# R3D2.net
KiCad netlist of a schematic drawn in EAGLE
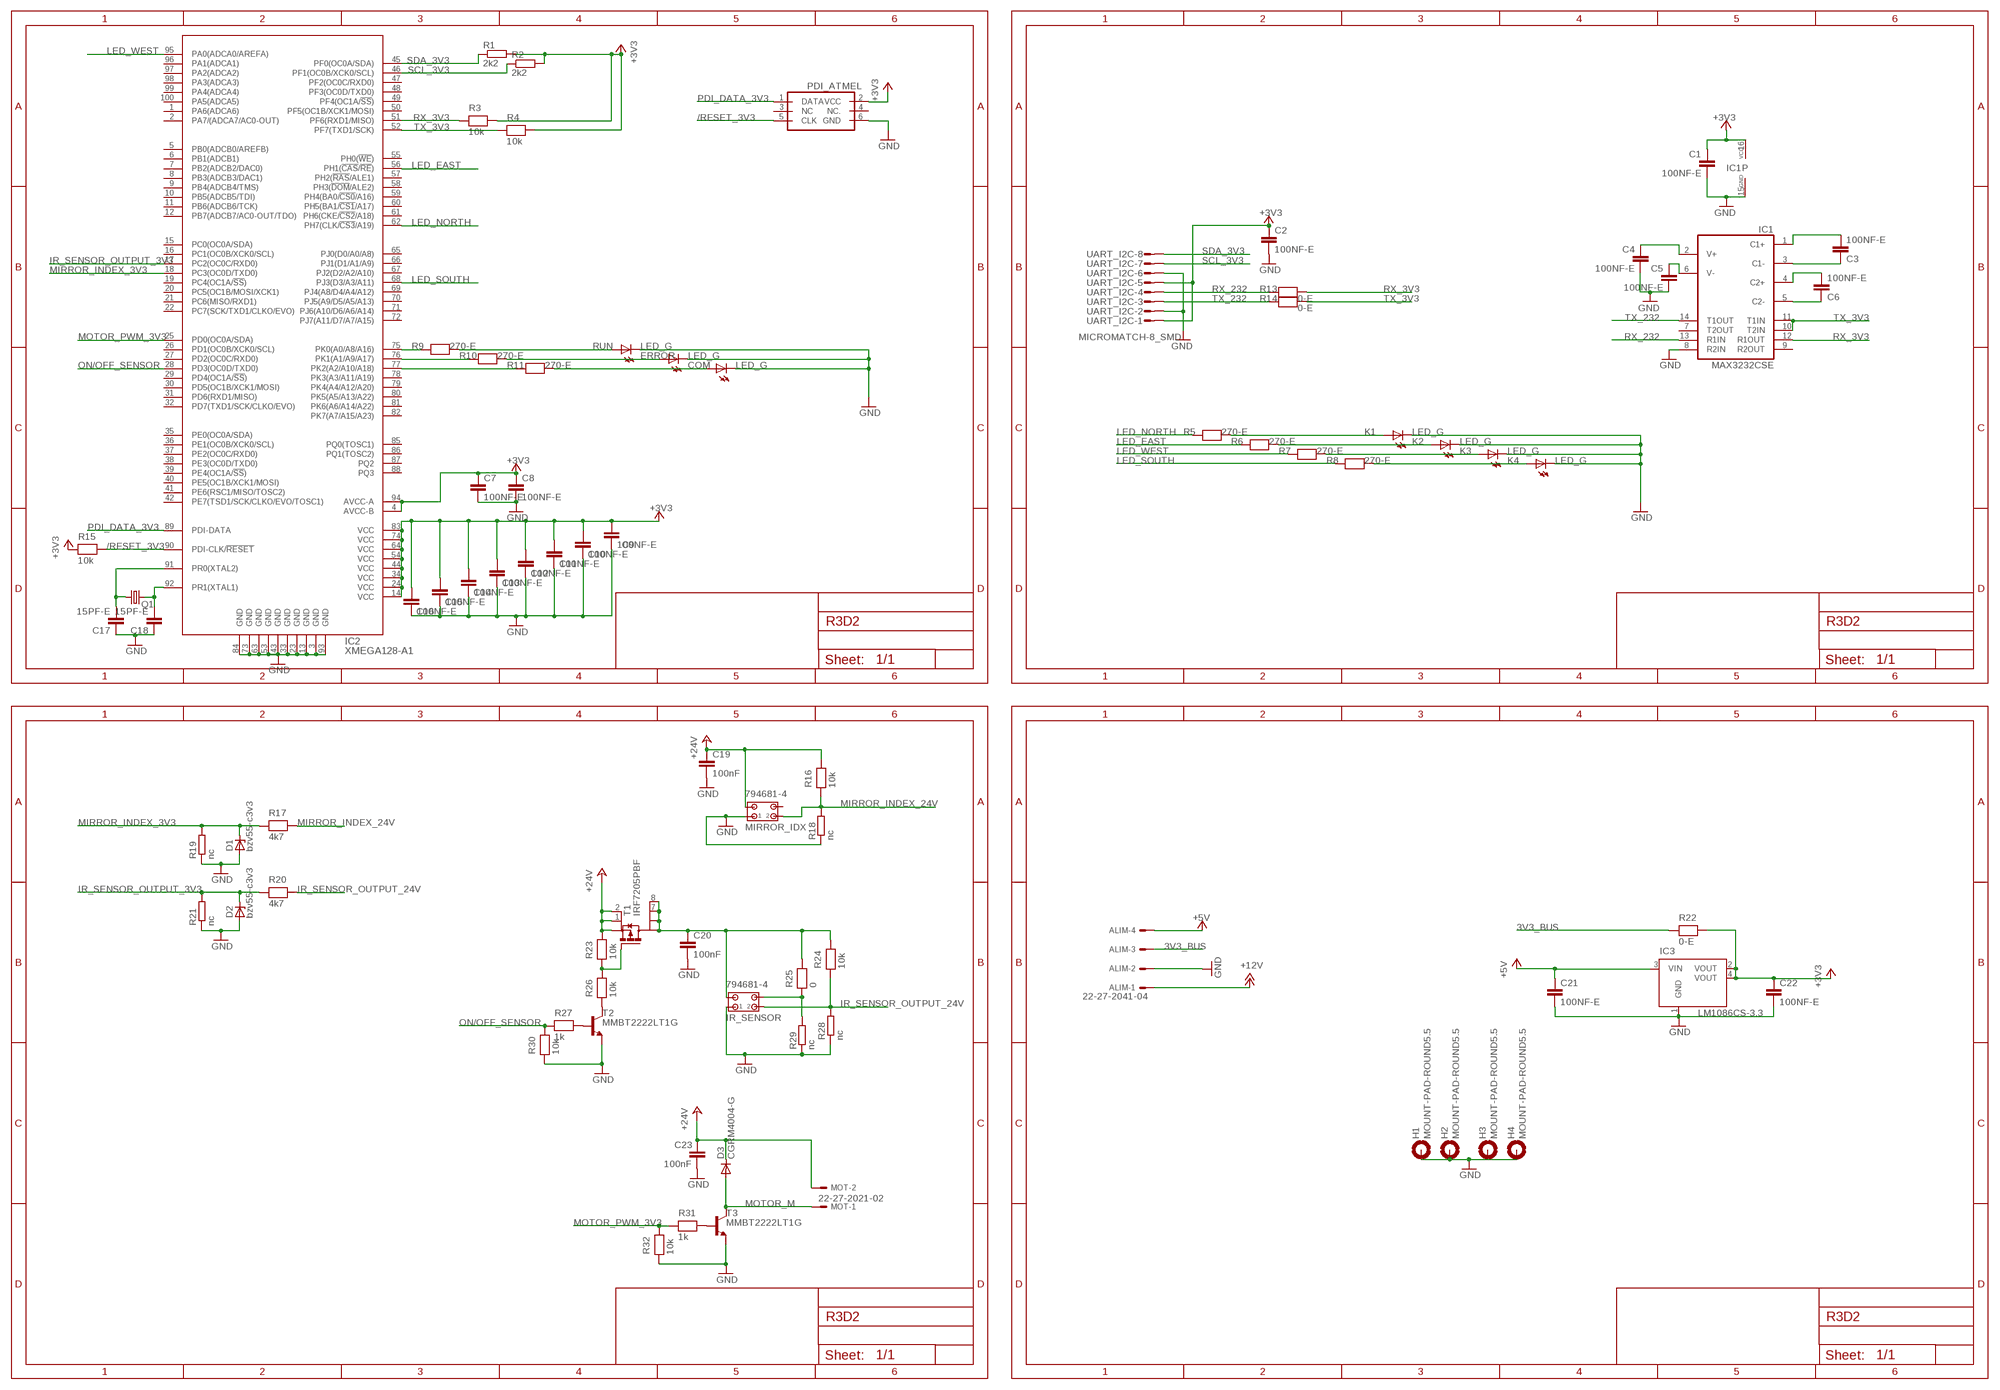
[diagram p0: schematic, sheet 1]

(export (version "E")
  (design (tool "Eeschema 10.0.6"))
  (components
    (comp (ref "ALIM")
      (value "22-27-2041-04")
      (footprint "eagle-import:6410-04")
      (libsource (lib "eagle-import") (part "22-?-0427-2041"))
    )
    (comp (ref "C1")
      (value "100NF-E")
      (footprint "eagle-import:C0805")
      (libsource (lib "eagle-import") (part "100NF-E"))
    )
    (comp (ref "C2")
      (value "100NF-E")
      (footprint "eagle-import:C0805")
      (libsource (lib "eagle-import") (part "100NF-E"))
    )
    (comp (ref "C3")
      (value "100NF-E")
      (footprint "eagle-import:C0805")
      (libsource (lib "eagle-import") (part "100NF-E"))
    )
    (comp (ref "C4")
      (value "100NF-E")
      (footprint "eagle-import:C0805")
      (libsource (lib "eagle-import") (part "100NF-E"))
    )
    (comp (ref "C5")
      (value "100NF-E")
      (footprint "eagle-import:C0805")
      (libsource (lib "eagle-import") (part "100NF-E"))
    )
    (comp (ref "C6")
      (value "100NF-E")
      (footprint "eagle-import:C0805")
      (libsource (lib "eagle-import") (part "100NF-E"))
    )
    (comp (ref "C7")
      (value "100NF-E")
      (footprint "eagle-import:C0805")
      (libsource (lib "eagle-import") (part "100NF-E"))
    )
    (comp (ref "C8")
      (value "100NF-E")
      (footprint "eagle-import:C0805")
      (libsource (lib "eagle-import") (part "100NF-E"))
    )
    (comp (ref "C9")
      (value "100NF-E")
      (footprint "eagle-import:C0805")
      (libsource (lib "eagle-import") (part "100NF-E"))
    )
    (comp (ref "C10")
      (value "100NF-E")
      (footprint "eagle-import:C0805")
      (libsource (lib "eagle-import") (part "100NF-E"))
    )
    (comp (ref "C11")
      (value "100NF-E")
      (footprint "eagle-import:C0805")
      (libsource (lib "eagle-import") (part "100NF-E"))
    )
    (comp (ref "C12")
      (value "100NF-E")
      (footprint "eagle-import:C0805")
      (libsource (lib "eagle-import") (part "100NF-E"))
    )
    (comp (ref "C13")
      (value "100NF-E")
      (footprint "eagle-import:C0805")
      (libsource (lib "eagle-import") (part "100NF-E"))
    )
    (comp (ref "C14")
      (value "100NF-E")
      (footprint "eagle-import:C0805")
      (libsource (lib "eagle-import") (part "100NF-E"))
    )
    (comp (ref "C15")
      (value "100NF-E")
      (footprint "eagle-import:C0805")
      (libsource (lib "eagle-import") (part "100NF-E"))
    )
    (comp (ref "C16")
      (value "100NF-E")
      (footprint "eagle-import:C0805")
      (libsource (lib "eagle-import") (part "100NF-E"))
    )
    (comp (ref "C17")
      (value "15PF-E")
      (footprint "eagle-import:C0805")
      (libsource (lib "eagle-import") (part "15PF-E"))
    )
    (comp (ref "C18")
      (value "15PF-E")
      (footprint "eagle-import:C0805")
      (libsource (lib "eagle-import") (part "15PF-E"))
    )
    (comp (ref "C19")
      (value "100nF")
      (footprint "eagle-import:C0805")
      (libsource (lib "eagle-import") (part "100NF-E"))
    )
    (comp (ref "C20")
      (value "100nF")
      (footprint "eagle-import:C0603")
      (libsource (lib "eagle-import") (part "100NF-F"))
    )
    (comp (ref "C21")
      (value "100NF-E")
      (footprint "eagle-import:C0805")
      (libsource (lib "eagle-import") (part "100NF-E"))
    )
    (comp (ref "C22")
      (value "100NF-E")
      (footprint "eagle-import:C0805")
      (libsource (lib "eagle-import") (part "100NF-E"))
    )
    (comp (ref "C23")
      (value "100nF")
      (footprint "eagle-import:C0805")
      (libsource (lib "eagle-import") (part "100NF-E"))
    )
    (comp (ref "COM")
      (value "LED_G")
      (footprint "eagle-import:CHIP-LED0805")
      (libsource (lib "eagle-import") (part "LED_G"))
    )
    (comp (ref "D1")
      (value "bzv55-c3v3")
      (footprint "eagle-import:SOD80C")
      (libsource (lib "eagle-import") (part "BZV55-C3V3SOD80C"))
    )
    (comp (ref "D2")
      (value "bzv55-c3v3")
      (footprint "eagle-import:SOD80C")
      (libsource (lib "eagle-import") (part "BZV55-C3V3SOD80C"))
    )
    (comp (ref "D3")
      (value "CGRM4004-G")
      (footprint "eagle-import:SOD-123_MINI-SMA")
      (libsource (lib "eagle-import") (part "CGRM400-G4"))
    )
    (comp (ref "ERROR")
      (value "LED_G")
      (footprint "eagle-import:CHIP-LED0805")
      (libsource (lib "eagle-import") (part "LED_G"))
    )
    (comp (ref "H1")
      (value "MOUNT-PAD-ROUND5.5")
      (footprint "eagle-import:5,5-PAD")
      (libsource (lib "eagle-import") (part "MOUNT-PAD-ROUND5.5"))
    )
    (comp (ref "H2")
      (value "MOUNT-PAD-ROUND5.5")
      (footprint "eagle-import:5,5-PAD")
      (libsource (lib "eagle-import") (part "MOUNT-PAD-ROUND5.5"))
    )
    (comp (ref "H3")
      (value "MOUNT-PAD-ROUND5.5")
      (footprint "eagle-import:5,5-PAD")
      (libsource (lib "eagle-import") (part "MOUNT-PAD-ROUND5.5"))
    )
    (comp (ref "H4")
      (value "MOUNT-PAD-ROUND5.5")
      (footprint "eagle-import:5,5-PAD")
      (libsource (lib "eagle-import") (part "MOUNT-PAD-ROUND5.5"))
    )
    (comp (ref "IC1")
      (value "MAX3232CSE")
      (footprint "eagle-import:SO16")
      (libsource (lib "eagle-import") (part "MAX3232SEC"))
    )
    (comp (ref "IC2")
      (value "XMEGA128-A1")
      (footprint "eagle-import:TQFP100")
      (libsource (lib "eagle-import") (part "XMEGA-A1TQFP"))
    )
    (comp (ref "IC3")
      (value "LM1086CS-3.3")
      (footprint "eagle-import:TO263")
      (libsource (lib "eagle-import") (part "LM1086CS-3.3"))
    )
    (comp (ref "IR_SENSOR")
      (value "794681-4")
      (footprint "eagle-import:794681-4")
      (libsource (lib "eagle-import") (part "794681-4"))
    )
    (comp (ref "K1")
      (value "LED_G")
      (footprint "eagle-import:CHIP-LED0805")
      (libsource (lib "eagle-import") (part "LED_G"))
    )
    (comp (ref "K2")
      (value "LED_G")
      (footprint "eagle-import:CHIP-LED0805")
      (libsource (lib "eagle-import") (part "LED_G"))
    )
    (comp (ref "K3")
      (value "LED_G")
      (footprint "eagle-import:CHIP-LED0805")
      (libsource (lib "eagle-import") (part "LED_G"))
    )
    (comp (ref "K4")
      (value "LED_G")
      (footprint "eagle-import:CHIP-LED0805")
      (libsource (lib "eagle-import") (part "LED_G"))
    )
    (comp (ref "MIRROR_IDX")
      (value "794681-4")
      (footprint "eagle-import:794681-4")
      (libsource (lib "eagle-import") (part "794681-4"))
    )
    (comp (ref "MOT")
      (value "22-27-2021-02")
      (footprint "eagle-import:6410-02")
      (libsource (lib "eagle-import") (part "22-?-0227-2021"))
    )
    (comp (ref "PDI_ATMEL")
      (value "PDI_ATMEL")
      (footprint "eagle-import:ML6")
      (libsource (lib "eagle-import") (part "PDI_ATMEL"))
    )
    (comp (ref "Q1")
      (value "CRYSTAL_16MHZ_HC49UP")
      (footprint "eagle-import:HC49UP")
      (libsource (lib "eagle-import") (part "CRYSTAL_16MHZ_HC49UP"))
    )
    (comp (ref "R1")
      (value "2k2")
      (footprint "eagle-import:R0603")
      (libsource (lib "eagle-import") (part "R-EU_R0603"))
    )
    (comp (ref "R2")
      (value "2k2")
      (footprint "eagle-import:R0603")
      (libsource (lib "eagle-import") (part "R-EU_R0603"))
    )
    (comp (ref "R3")
      (value "10k")
      (footprint "eagle-import:R0603")
      (libsource (lib "eagle-import") (part "10K-F"))
    )
    (comp (ref "R4")
      (value "10k")
      (footprint "eagle-import:R0603")
      (libsource (lib "eagle-import") (part "10K-F"))
    )
    (comp (ref "R5")
      (value "270-E")
      (footprint "eagle-import:R0805")
      (libsource (lib "eagle-import") (part "270-E"))
    )
    (comp (ref "R6")
      (value "270-E")
      (footprint "eagle-import:R0805")
      (libsource (lib "eagle-import") (part "270-E"))
    )
    (comp (ref "R7")
      (value "270-E")
      (footprint "eagle-import:R0805")
      (libsource (lib "eagle-import") (part "270-E"))
    )
    (comp (ref "R8")
      (value "270-E")
      (footprint "eagle-import:R0805")
      (libsource (lib "eagle-import") (part "270-E"))
    )
    (comp (ref "R9")
      (value "270-E")
      (footprint "eagle-import:R0805")
      (libsource (lib "eagle-import") (part "270-E"))
    )
    (comp (ref "R10")
      (value "270-E")
      (footprint "eagle-import:R0805")
      (libsource (lib "eagle-import") (part "270-E"))
    )
    (comp (ref "R11")
      (value "270-E")
      (footprint "eagle-import:R0805")
      (libsource (lib "eagle-import") (part "270-E"))
    )
    (comp (ref "R13")
      (value "0-E")
      (footprint "eagle-import:R0805")
      (libsource (lib "eagle-import") (part "0-E"))
    )
    (comp (ref "R14")
      (value "0-E")
      (footprint "eagle-import:R0805")
      (libsource (lib "eagle-import") (part "0-E"))
    )
    (comp (ref "R15")
      (value "10k")
      (footprint "eagle-import:R0603")
      (libsource (lib "eagle-import") (part "10K-F"))
    )
    (comp (ref "R16")
      (value "10k")
      (footprint "eagle-import:R0603")
      (libsource (lib "eagle-import") (part "10K-F"))
    )
    (comp (ref "R17")
      (value "4k7")
      (footprint "eagle-import:R0805")
      (libsource (lib "eagle-import") (part "4K7-E"))
    )
    (comp (ref "R18")
      (value "nc")
      (footprint "eagle-import:R0805")
      (libsource (lib "eagle-import") (part "R-EU_R0805"))
    )
    (comp (ref "R19")
      (value "nc")
      (footprint "eagle-import:R0603")
      (libsource (lib "eagle-import") (part "R-EU_R0603"))
    )
    (comp (ref "R20")
      (value "4k7")
      (footprint "eagle-import:R0805")
      (libsource (lib "eagle-import") (part "4K7-E"))
    )
    (comp (ref "R21")
      (value "nc")
      (footprint "eagle-import:R0603")
      (libsource (lib "eagle-import") (part "R-EU_R0603"))
    )
    (comp (ref "R22")
      (value "0-E")
      (footprint "eagle-import:R0805")
      (libsource (lib "eagle-import") (part "0-E"))
    )
    (comp (ref "R23")
      (value "10k")
      (footprint "eagle-import:R0603")
      (libsource (lib "eagle-import") (part "10K-F"))
    )
    (comp (ref "R24")
      (value "10k")
      (footprint "eagle-import:R0603")
      (libsource (lib "eagle-import") (part "10K-F"))
    )
    (comp (ref "R25")
      (value "0")
      (footprint "eagle-import:R0603")
      (libsource (lib "eagle-import") (part "0-F"))
    )
    (comp (ref "R26")
      (value "10k")
      (footprint "eagle-import:R0603")
      (libsource (lib "eagle-import") (part "10K-F"))
    )
    (comp (ref "R27")
      (value "1k")
      (footprint "eagle-import:R0603")
      (libsource (lib "eagle-import") (part "1K-F"))
    )
    (comp (ref "R28")
      (value "nc")
      (footprint "eagle-import:R0603")
      (libsource (lib "eagle-import") (part "R-EU_R0603"))
    )
    (comp (ref "R29")
      (value "nc")
      (footprint "eagle-import:R0603")
      (libsource (lib "eagle-import") (part "R-EU_R0603"))
    )
    (comp (ref "R30")
      (value "10k")
      (footprint "eagle-import:R0603")
      (libsource (lib "eagle-import") (part "10K-F"))
    )
    (comp (ref "R31")
      (value "1k")
      (footprint "eagle-import:R0603")
      (libsource (lib "eagle-import") (part "1K-F"))
    )
    (comp (ref "R32")
      (value "10k")
      (footprint "eagle-import:R0603")
      (libsource (lib "eagle-import") (part "10K-F"))
    )
    (comp (ref "RUN")
      (value "LED_G")
      (footprint "eagle-import:CHIP-LED0805")
      (libsource (lib "eagle-import") (part "LED_G"))
    )
    (comp (ref "T1")
      (value "IRF7205PBF")
      (footprint "eagle-import:SO8")
      (libsource (lib "eagle-import") (part "IRF7205PBF"))
    )
    (comp (ref "T2")
      (value "MMBT2222LT1G")
      (footprint "eagle-import:SOT23-BEC")
      (libsource (lib "eagle-import") (part "-NPN-SOT23-BECMMBT2222ALT1"))
    )
    (comp (ref "T3")
      (value "MMBT2222LT1G")
      (footprint "eagle-import:SOT23-BEC")
      (libsource (lib "eagle-import") (part "-NPN-SOT23-BECMMBT2222ALT1"))
    )
    (comp (ref "UART_I2C")
      (value "MICROMATCH-8_SMD")
      (footprint "eagle-import:MICROMATCH-8_SMD")
      (libsource (lib "eagle-import") (part "MICROMATCH-8_SMD"))
    )
  )
  (nets
    (net (code "1") (name "+3V3") (class "Default")
      (node (ref "C1") (pin "1") (pinfunction "1_1") (pintype "passive"))
      (node (ref "C10") (pin "1") (pinfunction "1_1") (pintype "passive"))
      (node (ref "C11") (pin "1") (pinfunction "1_1") (pintype "passive"))
      (node (ref "C12") (pin "1") (pinfunction "1_1") (pintype "passive"))
      (node (ref "C13") (pin "1") (pinfunction "1_1") (pintype "passive"))
      (node (ref "C14") (pin "1") (pinfunction "1_1") (pintype "passive"))
      (node (ref "C15") (pin "1") (pinfunction "1_1") (pintype "passive"))
      (node (ref "C16") (pin "1") (pinfunction "1_1") (pintype "passive"))
      (node (ref "C2") (pin "1") (pinfunction "1_1") (pintype "passive"))
      (node (ref "C22") (pin "1") (pinfunction "1_1") (pintype "passive"))
      (node (ref "C7") (pin "1") (pinfunction "1_1") (pintype "passive"))
      (node (ref "C8") (pin "1") (pinfunction "1_1") (pintype "passive"))
      (node (ref "C9") (pin "1") (pinfunction "1_1") (pintype "passive"))
      (node (ref "IC1") (pin "16") (pinfunction "VCC_16") (pintype "power_in"))
      (node (ref "IC2") (pin "14") (pinfunction "VCC_14") (pintype "power_in"))
      (node (ref "IC2") (pin "24") (pinfunction "VCC_24") (pintype "power_in"))
      (node (ref "IC2") (pin "34") (pinfunction "VCC_34") (pintype "power_in"))
      (node (ref "IC2") (pin "4") (pinfunction "AVCC-B_4") (pintype "power_in"))
      (node (ref "IC2") (pin "44") (pinfunction "VCC_44") (pintype "power_in"))
      (node (ref "IC2") (pin "54") (pinfunction "VCC_54") (pintype "power_in"))
      (node (ref "IC2") (pin "64") (pinfunction "VCC_64") (pintype "power_in"))
      (node (ref "IC2") (pin "74") (pinfunction "VCC_74") (pintype "power_in"))
      (node (ref "IC2") (pin "83") (pinfunction "VCC_83") (pintype "power_in"))
      (node (ref "IC2") (pin "94") (pinfunction "AVCC-A_94") (pintype "power_in"))
      (node (ref "IC3") (pin "2") (pinfunction "VOUT_2") (pintype "bidirectional"))
      (node (ref "IC3") (pin "4") (pinfunction "VOUT_4") (pintype "bidirectional"))
      (node (ref "PDI_ATMEL") (pin "2") (pinfunction "VCC_2") (pintype "passive"))
      (node (ref "R1") (pin "2") (pinfunction "2_2") (pintype "passive"))
      (node (ref "R15") (pin "1") (pinfunction "1_1") (pintype "bidirectional"))
      (node (ref "R2") (pin "2") (pinfunction "2_2") (pintype "passive"))
      (node (ref "R22") (pin "2") (pinfunction "2_2") (pintype "bidirectional"))
      (node (ref "R3") (pin "2") (pinfunction "2_2") (pintype "bidirectional"))
      (node (ref "R4") (pin "2") (pinfunction "2_2") (pintype "bidirectional"))
      (node (ref "UART_I2C") (pin "1") (pinfunction "S_1") (pintype "passive"))
      (node (ref "UART_I2C") (pin "5") (pinfunction "S_5") (pintype "passive"))
    )
    (net (code "2") (name "+5V") (class "Default")
      (node (ref "ALIM") (pin "4") (pinfunction "S_4") (pintype "passive"))
      (node (ref "C21") (pin "1") (pinfunction "1_1") (pintype "passive"))
      (node (ref "IC3") (pin "3") (pinfunction "VIN_3") (pintype "bidirectional"))
    )
    (net (code "3") (name "+12V") (class "Default")
      (node (ref "ALIM") (pin "1") (pinfunction "S_1") (pintype "passive"))
    )
    (net (code "4") (name "+24V") (class "Default")
      (node (ref "C19") (pin "1") (pinfunction "1_1") (pintype "passive"))
      (node (ref "C23") (pin "1") (pinfunction "1_1") (pintype "passive"))
      (node (ref "D3") (pin "C") (pinfunction "C_C") (pintype "passive"))
      (node (ref "MIRROR_IDX") (pin "3") (pinfunction "3_3") (pintype "passive"))
      (node (ref "MOT") (pin "2") (pinfunction "S_2") (pintype "passive"))
      (node (ref "R16") (pin "2") (pinfunction "2_2") (pintype "bidirectional"))
      (node (ref "R23") (pin "2") (pinfunction "2_2") (pintype "bidirectional"))
      (node (ref "T1") (pin "1") (pinfunction "S_1") (pintype "power_in"))
      (node (ref "T1") (pin "2") (pinfunction "S_2") (pintype "power_in"))
      (node (ref "T1") (pin "3") (pinfunction "S_3") (pintype "power_in"))
    )
    (net (code "5") (name "/3V3_BUS") (class "Default")
      (node (ref "ALIM") (pin "3") (pinfunction "S_3") (pintype "passive"))
      (node (ref "R22") (pin "1") (pinfunction "1_1") (pintype "bidirectional"))
    )
    (net (code "6") (name "/IR_SENSOR_OUTPUT_3V3") (class "Default")
      (node (ref "D2") (pin "C") (pinfunction "C_C") (pintype "passive"))
      (node (ref "IC2") (pin "17") (pinfunction "PC2(OC0C/RXD0)_17") (pintype "bidirectional"))
      (node (ref "R20") (pin "1") (pinfunction "1_1") (pintype "bidirectional"))
      (node (ref "R21") (pin "2") (pinfunction "2_2") (pintype "passive"))
    )
    (net (code "7") (name "/IR_SENSOR_OUTPUT_24V") (class "Default")
      (node (ref "IR_SENSOR") (pin "2") (pinfunction "2_2") (pintype "passive"))
      (node (ref "R20") (pin "2") (pinfunction "2_2") (pintype "bidirectional"))
      (node (ref "R24") (pin "1") (pinfunction "1_1") (pintype "bidirectional"))
      (node (ref "R28") (pin "2") (pinfunction "2_2") (pintype "passive"))
    )
    (net (code "8") (name "/LED_EAST") (class "Default")
      (node (ref "IC2") (pin "56") (pinfunction "PH1(~{CAS}/~{RE})_56") (pintype "bidirectional"))
      (node (ref "R6") (pin "1") (pinfunction "1_1") (pintype "bidirectional"))
    )
    (net (code "9") (name "/LED_NORTH") (class "Default")
      (node (ref "IC2") (pin "62") (pinfunction "PH7(CLK/~{CS3}/A19)_62") (pintype "bidirectional"))
      (node (ref "R5") (pin "1") (pinfunction "1_1") (pintype "bidirectional"))
    )
    (net (code "10") (name "/LED_SOUTH") (class "Default")
      (node (ref "IC2") (pin "68") (pinfunction "PJ3(D3/A3/A11)_68") (pintype "bidirectional"))
      (node (ref "R8") (pin "1") (pinfunction "1_1") (pintype "bidirectional"))
    )
    (net (code "11") (name "/LED_WEST") (class "Default")
      (node (ref "IC2") (pin "95") (pinfunction "PA0(ADCA0/AREFA)_95") (pintype "bidirectional"))
      (node (ref "R7") (pin "1") (pinfunction "1_1") (pintype "bidirectional"))
    )
    (net (code "12") (name "/MIRROR_INDEX_3V3") (class "Default")
      (node (ref "D1") (pin "C") (pinfunction "C_C") (pintype "passive"))
      (node (ref "IC2") (pin "18") (pinfunction "PC3(OC0D/TXD0)_18") (pintype "bidirectional"))
      (node (ref "R17") (pin "1") (pinfunction "1_1") (pintype "bidirectional"))
      (node (ref "R19") (pin "2") (pinfunction "2_2") (pintype "passive"))
    )
    (net (code "13") (name "/MIRROR_INDEX_24V") (class "Default")
      (node (ref "MIRROR_IDX") (pin "2") (pinfunction "2_2") (pintype "passive"))
      (node (ref "R16") (pin "1") (pinfunction "1_1") (pintype "bidirectional"))
      (node (ref "R17") (pin "2") (pinfunction "2_2") (pintype "bidirectional"))
      (node (ref "R18") (pin "2") (pinfunction "2_2") (pintype "passive"))
    )
    (net (code "14") (name "/MOTOR_M") (class "Default")
      (node (ref "D3") (pin "A") (pinfunction "A_A") (pintype "passive"))
      (node (ref "MOT") (pin "1") (pinfunction "S_1") (pintype "passive"))
      (node (ref "T3") (pin "C") (pinfunction "C_C") (pintype "passive"))
    )
    (net (code "15") (name "/MOTOR_PWM_3V3") (class "Default")
      (node (ref "IC2") (pin "25") (pinfunction "PD0(OC0A/SDA)_25") (pintype "bidirectional"))
      (node (ref "R31") (pin "1") (pinfunction "1_1") (pintype "bidirectional"))
      (node (ref "R32") (pin "2") (pinfunction "2_2") (pintype "bidirectional"))
    )
    (net (code "16") (name "/ON{slash}OFF_SENSOR") (class "Default")
      (node (ref "IC2") (pin "28") (pinfunction "PD3(OC0D/TXD0)_28") (pintype "bidirectional"))
      (node (ref "R27") (pin "1") (pinfunction "1_1") (pintype "bidirectional"))
      (node (ref "R30") (pin "2") (pinfunction "2_2") (pintype "bidirectional"))
    )
    (net (code "17") (name "/PDI_DATA_3V3") (class "Default")
      (node (ref "IC2") (pin "89") (pinfunction "PDI-DATA_89") (pintype "bidirectional"))
      (node (ref "PDI_ATMEL") (pin "1") (pinfunction "DATA_1") (pintype "passive"))
    )
    (net (code "18") (name "/RX_3V3") (class "Default")
      (node (ref "IC1") (pin "12") (pinfunction "R1OUT_12") (pintype "output"))
      (node (ref "IC2") (pin "51") (pinfunction "PF6(RXD1/MISO)_51") (pintype "bidirectional"))
      (node (ref "R13") (pin "2") (pinfunction "2_2") (pintype "bidirectional"))
      (node (ref "R3") (pin "1") (pinfunction "1_1") (pintype "bidirectional"))
    )
    (net (code "19") (name "/RX_232") (class "Default")
      (node (ref "IC1") (pin "13") (pinfunction "R1IN_13") (pintype "input"))
      (node (ref "R13") (pin "1") (pinfunction "1_1") (pintype "bidirectional"))
      (node (ref "UART_I2C") (pin "4") (pinfunction "S_4") (pintype "passive"))
    )
    (net (code "20") (name "/SCL_3V3") (class "Default")
      (node (ref "IC2") (pin "46") (pinfunction "PF1(OC0B/XCK0/SCL)_46") (pintype "bidirectional"))
      (node (ref "R2") (pin "1") (pinfunction "1_1") (pintype "passive"))
      (node (ref "UART_I2C") (pin "7") (pinfunction "S_7") (pintype "passive"))
    )
    (net (code "21") (name "/SDA_3V3") (class "Default")
      (node (ref "IC2") (pin "45") (pinfunction "PF0(OC0A/SDA)_45") (pintype "bidirectional"))
      (node (ref "R1") (pin "1") (pinfunction "1_1") (pintype "passive"))
      (node (ref "UART_I2C") (pin "8") (pinfunction "S_8") (pintype "passive"))
    )
    (net (code "22") (name "/TX_3V3") (class "Default")
      (node (ref "IC1") (pin "10") (pinfunction "T2IN_10") (pintype "input"))
      (node (ref "IC1") (pin "11") (pinfunction "T1IN_11") (pintype "input"))
      (node (ref "IC2") (pin "52") (pinfunction "PF7(TXD1/SCK)_52") (pintype "bidirectional"))
      (node (ref "R14") (pin "2") (pinfunction "2_2") (pintype "bidirectional"))
      (node (ref "R4") (pin "1") (pinfunction "1_1") (pintype "bidirectional"))
    )
    (net (code "23") (name "/TX_232") (class "Default")
      (node (ref "IC1") (pin "14") (pinfunction "T1OUT_14") (pintype "output"))
      (node (ref "R14") (pin "1") (pinfunction "1_1") (pintype "bidirectional"))
      (node (ref "UART_I2C") (pin "3") (pinfunction "S_3") (pintype "passive"))
    )
    (net (code "24") (name "/{slash}RESET_3V3") (class "Default")
      (node (ref "IC2") (pin "90") (pinfunction "PDI-CLK/~{RESET}_90") (pintype "input"))
      (node (ref "PDI_ATMEL") (pin "5") (pinfunction "CLK_5") (pintype "passive"))
      (node (ref "R15") (pin "2") (pinfunction "2_2") (pintype "bidirectional"))
    )
    (net (code "25") (name "GND") (class "Default")
      (node (ref "ALIM") (pin "2") (pinfunction "S_2") (pintype "passive"))
      (node (ref "C1") (pin "2") (pinfunction "2_2") (pintype "passive"))
      (node (ref "C10") (pin "2") (pinfunction "2_2") (pintype "passive"))
      (node (ref "C11") (pin "2") (pinfunction "2_2") (pintype "passive"))
      (node (ref "C12") (pin "2") (pinfunction "2_2") (pintype "passive"))
      (node (ref "C13") (pin "2") (pinfunction "2_2") (pintype "passive"))
      (node (ref "C14") (pin "2") (pinfunction "2_2") (pintype "passive"))
      (node (ref "C15") (pin "2") (pinfunction "2_2") (pintype "passive"))
      (node (ref "C16") (pin "2") (pinfunction "2_2") (pintype "passive"))
      (node (ref "C17") (pin "1") (pinfunction "1_1") (pintype "passive"))
      (node (ref "C18") (pin "1") (pinfunction "1_1") (pintype "passive"))
      (node (ref "C19") (pin "2") (pinfunction "2_2") (pintype "passive"))
      (node (ref "C2") (pin "2") (pinfunction "2_2") (pintype "passive"))
      (node (ref "C20") (pin "2") (pinfunction "2_2") (pintype "passive"))
      (node (ref "C21") (pin "2") (pinfunction "2_2") (pintype "passive"))
      (node (ref "C22") (pin "2") (pinfunction "2_2") (pintype "passive"))
      (node (ref "C23") (pin "2") (pinfunction "2_2") (pintype "passive"))
      (node (ref "C4") (pin "2") (pinfunction "2_2") (pintype "passive"))
      (node (ref "C5") (pin "2") (pinfunction "2_2") (pintype "passive"))
      (node (ref "C7") (pin "2") (pinfunction "2_2") (pintype "passive"))
      (node (ref "C8") (pin "2") (pinfunction "2_2") (pintype "passive"))
      (node (ref "C9") (pin "2") (pinfunction "2_2") (pintype "passive"))
      (node (ref "COM") (pin "C") (pinfunction "C_C") (pintype "passive"))
      (node (ref "D1") (pin "A") (pinfunction "A_A") (pintype "passive"))
      (node (ref "D2") (pin "A") (pinfunction "A_A") (pintype "passive"))
      (node (ref "ERROR") (pin "C") (pinfunction "C_C") (pintype "passive"))
      (node (ref "H1") (pin "B5,5") (pinfunction "MOUNT_B5,5") (pintype "passive"))
      (node (ref "H2") (pin "B5,5") (pinfunction "MOUNT_B5,5") (pintype "passive"))
      (node (ref "H3") (pin "B5,5") (pinfunction "MOUNT_B5,5") (pintype "passive"))
      (node (ref "H4") (pin "B5,5") (pinfunction "MOUNT_B5,5") (pintype "passive"))
      (node (ref "IC1") (pin "15") (pinfunction "GND_15") (pintype "power_in"))
      (node (ref "IC1") (pin "8") (pinfunction "R2IN_8") (pintype "input"))
      (node (ref "IC2") (pin "13") (pinfunction "GND_13") (pintype "power_in"))
      (node (ref "IC2") (pin "23") (pinfunction "GND_23") (pintype "power_in"))
      (node (ref "IC2") (pin "3") (pinfunction "GND_3") (pintype "power_in"))
      (node (ref "IC2") (pin "33") (pinfunction "GND_33") (pintype "power_in"))
      (node (ref "IC2") (pin "43") (pinfunction "GND_43") (pintype "power_in"))
      (node (ref "IC2") (pin "53") (pinfunction "GND_53") (pintype "power_in"))
      (node (ref "IC2") (pin "63") (pinfunction "GND_63") (pintype "power_in"))
      (node (ref "IC2") (pin "73") (pinfunction "GND_73") (pintype "power_in"))
      (node (ref "IC2") (pin "84") (pinfunction "GND_84") (pintype "power_in"))
      (node (ref "IC2") (pin "93") (pinfunction "GND_93") (pintype "power_in"))
      (node (ref "IC3") (pin "1") (pinfunction "GND_1") (pintype "bidirectional"))
      (node (ref "IR_SENSOR") (pin "1") (pinfunction "1_1") (pintype "passive"))
      (node (ref "K1") (pin "C") (pinfunction "C_C") (pintype "passive"))
      (node (ref "K2") (pin "C") (pinfunction "C_C") (pintype "passive"))
      (node (ref "K3") (pin "C") (pinfunction "C_C") (pintype "passive"))
      (node (ref "K4") (pin "C") (pinfunction "C_C") (pintype "passive"))
      (node (ref "MIRROR_IDX") (pin "1") (pinfunction "1_1") (pintype "passive"))
      (node (ref "PDI_ATMEL") (pin "6") (pinfunction "GND_6") (pintype "passive"))
      (node (ref "R18") (pin "1") (pinfunction "1_1") (pintype "passive"))
      (node (ref "R19") (pin "1") (pinfunction "1_1") (pintype "passive"))
      (node (ref "R21") (pin "1") (pinfunction "1_1") (pintype "passive"))
      (node (ref "R28") (pin "1") (pinfunction "1_1") (pintype "passive"))
      (node (ref "R29") (pin "1") (pinfunction "1_1") (pintype "passive"))
      (node (ref "R30") (pin "1") (pinfunction "1_1") (pintype "bidirectional"))
      (node (ref "R32") (pin "1") (pinfunction "1_1") (pintype "bidirectional"))
      (node (ref "RUN") (pin "C") (pinfunction "C_C") (pintype "passive"))
      (node (ref "T2") (pin "E") (pinfunction "E_E") (pintype "passive"))
      (node (ref "T3") (pin "E") (pinfunction "E_E") (pintype "passive"))
      (node (ref "UART_I2C") (pin "2") (pinfunction "S_2") (pintype "passive"))
      (node (ref "UART_I2C") (pin "6") (pinfunction "S_6") (pintype "passive"))
    )
    (net (code "26") (name "Net-(C20-Pad1)") (class "Default")
      (node (ref "C20") (pin "1") (pinfunction "1_1") (pintype "passive"))
      (node (ref "IR_SENSOR") (pin "3") (pinfunction "3_3") (pintype "passive"))
      (node (ref "R24") (pin "2") (pinfunction "2_2") (pintype "bidirectional"))
      (node (ref "R25") (pin "2") (pinfunction "2_2") (pintype "bidirectional"))
      (node (ref "T1") (pin "5") (pinfunction "D_5") (pintype "power_in"))
      (node (ref "T1") (pin "6") (pinfunction "D_6") (pintype "power_in"))
      (node (ref "T1") (pin "7") (pinfunction "D_7") (pintype "power_in"))
      (node (ref "T1") (pin "8") (pinfunction "D_8") (pintype "power_in"))
    )
    (net (code "27") (name "Net-(COM-PadA)") (class "Default")
      (node (ref "COM") (pin "A") (pinfunction "A_A") (pintype "passive"))
      (node (ref "R11") (pin "2") (pinfunction "2_2") (pintype "bidirectional"))
    )
    (net (code "28") (name "Net-(ERROR-PadA)") (class "Default")
      (node (ref "ERROR") (pin "A") (pinfunction "A_A") (pintype "passive"))
      (node (ref "R10") (pin "2") (pinfunction "2_2") (pintype "bidirectional"))
    )
    (net (code "29") (name "Net-(IC1A-C1+)") (class "Default")
      (node (ref "C3") (pin "1") (pinfunction "1_1") (pintype "passive"))
      (node (ref "IC1") (pin "1") (pinfunction "C1+_1") (pintype "bidirectional"))
    )
    (net (code "30") (name "Net-(IC1A-C1-)") (class "Default")
      (node (ref "C3") (pin "2") (pinfunction "2_2") (pintype "passive"))
      (node (ref "IC1") (pin "3") (pinfunction "C1-_3") (pintype "bidirectional"))
    )
    (net (code "31") (name "Net-(IC1A-C2+)") (class "Default")
      (node (ref "C6") (pin "1") (pinfunction "1_1") (pintype "passive"))
      (node (ref "IC1") (pin "4") (pinfunction "C2+_4") (pintype "bidirectional"))
    )
    (net (code "32") (name "Net-(IC1A-C2-)") (class "Default")
      (node (ref "C6") (pin "2") (pinfunction "2_2") (pintype "passive"))
      (node (ref "IC1") (pin "5") (pinfunction "C2-_5") (pintype "bidirectional"))
    )
    (net (code "33") (name "Net-(IC1A-V+)") (class "Default")
      (node (ref "C4") (pin "1") (pinfunction "1_1") (pintype "passive"))
      (node (ref "IC1") (pin "2") (pinfunction "V+_2") (pintype "bidirectional"))
    )
    (net (code "34") (name "Net-(IC1A-V-)") (class "Default")
      (node (ref "C5") (pin "1") (pinfunction "1_1") (pintype "passive"))
      (node (ref "IC1") (pin "6") (pinfunction "V-_6") (pintype "bidirectional"))
    )
    (net (code "35") (name "Net-(IC2-PK0(A0{slash}A8{slash}A16))") (class "Default")
      (node (ref "IC2") (pin "75") (pinfunction "PK0(A0/A8/A16)_75") (pintype "bidirectional"))
      (node (ref "R9") (pin "1") (pinfunction "1_1") (pintype "bidirectional"))
    )
    (net (code "36") (name "Net-(IC2-PK1(A1{slash}A9{slash}A17))") (class "Default")
      (node (ref "IC2") (pin "76") (pinfunction "PK1(A1/A9/A17)_76") (pintype "bidirectional"))
      (node (ref "R10") (pin "1") (pinfunction "1_1") (pintype "bidirectional"))
    )
    (net (code "37") (name "Net-(IC2-PK2(A2{slash}A10{slash}A18))") (class "Default")
      (node (ref "IC2") (pin "77") (pinfunction "PK2(A2/A10/A18)_77") (pintype "bidirectional"))
      (node (ref "R11") (pin "1") (pinfunction "1_1") (pintype "bidirectional"))
    )
    (net (code "38") (name "Net-(IC2-PR0(XTAL2))") (class "Default")
      (node (ref "C17") (pin "2") (pinfunction "2_2") (pintype "passive"))
      (node (ref "IC2") (pin "91") (pinfunction "PR0(XTAL2)_91") (pintype "bidirectional"))
      (node (ref "Q1") (pin "1") (pinfunction "1_1") (pintype "passive"))
    )
    (net (code "39") (name "Net-(IC2-PR1(XTAL1))") (class "Default")
      (node (ref "C18") (pin "2") (pinfunction "2_2") (pintype "passive"))
      (node (ref "IC2") (pin "92") (pinfunction "PR1(XTAL1)_92") (pintype "bidirectional"))
      (node (ref "Q1") (pin "2") (pinfunction "2_2") (pintype "passive"))
    )
    (net (code "40") (name "Net-(IR_SENSOR-Pad4)") (class "Default")
      (node (ref "IR_SENSOR") (pin "4") (pinfunction "4_4") (pintype "passive"))
      (node (ref "R25") (pin "1") (pinfunction "1_1") (pintype "bidirectional"))
      (node (ref "R29") (pin "2") (pinfunction "2_2") (pintype "passive"))
    )
    (net (code "41") (name "Net-(K1-PadA)") (class "Default")
      (node (ref "K1") (pin "A") (pinfunction "A_A") (pintype "passive"))
      (node (ref "R5") (pin "2") (pinfunction "2_2") (pintype "bidirectional"))
    )
    (net (code "42") (name "Net-(K2-PadA)") (class "Default")
      (node (ref "K2") (pin "A") (pinfunction "A_A") (pintype "passive"))
      (node (ref "R6") (pin "2") (pinfunction "2_2") (pintype "bidirectional"))
    )
    (net (code "43") (name "Net-(K3-PadA)") (class "Default")
      (node (ref "K3") (pin "A") (pinfunction "A_A") (pintype "passive"))
      (node (ref "R7") (pin "2") (pinfunction "2_2") (pintype "bidirectional"))
    )
    (net (code "44") (name "Net-(K4-PadA)") (class "Default")
      (node (ref "K4") (pin "A") (pinfunction "A_A") (pintype "passive"))
      (node (ref "R8") (pin "2") (pinfunction "2_2") (pintype "bidirectional"))
    )
    (net (code "45") (name "Net-(R9-Pad2)") (class "Default")
      (node (ref "R9") (pin "2") (pinfunction "2_2") (pintype "bidirectional"))
      (node (ref "RUN") (pin "A") (pinfunction "A_A") (pintype "passive"))
    )
    (net (code "46") (name "Net-(R26-Pad1)") (class "Default")
      (node (ref "R26") (pin "1") (pinfunction "1_1") (pintype "bidirectional"))
      (node (ref "T2") (pin "C") (pinfunction "C_C") (pintype "passive"))
    )
    (net (code "47") (name "Net-(R27-Pad2)") (class "Default")
      (node (ref "R27") (pin "2") (pinfunction "2_2") (pintype "bidirectional"))
      (node (ref "T2") (pin "B") (pinfunction "B_B") (pintype "passive"))
    )
    (net (code "48") (name "Net-(R31-Pad2)") (class "Default")
      (node (ref "R31") (pin "2") (pinfunction "2_2") (pintype "bidirectional"))
      (node (ref "T3") (pin "B") (pinfunction "B_B") (pintype "passive"))
    )
    (net (code "49") (name "Net-(T1-G)") (class "Default")
      (node (ref "R23") (pin "1") (pinfunction "1_1") (pintype "bidirectional"))
      (node (ref "R26") (pin "2") (pinfunction "2_2") (pintype "bidirectional"))
      (node (ref "T1") (pin "4") (pinfunction "G_4") (pintype "bidirectional"))
    )
    (net (code "50") (name "unconnected-(IC1A-R2OUT-Pad9)") (class "Default")
      (node (ref "IC1") (pin "9") (pinfunction "R2OUT_9") (pintype "output"))
    )
    (net (code "51") (name "unconnected-(IC1A-T2OUT-Pad7)") (class "Default")
      (node (ref "IC1") (pin "7") (pinfunction "T2OUT_7") (pintype "output"))
    )
    (net (code "52") (name "unconnected-(IC2-PA1(ADCA1)-Pad96)") (class "Default")
      (node (ref "IC2") (pin "96") (pinfunction "PA1(ADCA1)_96") (pintype "bidirectional"))
    )
    (net (code "53") (name "unconnected-(IC2-PA2(ADCA2)-Pad97)") (class "Default")
      (node (ref "IC2") (pin "97") (pinfunction "PA2(ADCA2)_97") (pintype "bidirectional"))
    )
    (net (code "54") (name "unconnected-(IC2-PA3(ADCA3)-Pad98)") (class "Default")
      (node (ref "IC2") (pin "98") (pinfunction "PA3(ADCA3)_98") (pintype "bidirectional"))
    )
    (net (code "55") (name "unconnected-(IC2-PA4(ADCA4)-Pad99)") (class "Default")
      (node (ref "IC2") (pin "99") (pinfunction "PA4(ADCA4)_99") (pintype "bidirectional"))
    )
    (net (code "56") (name "unconnected-(IC2-PA5(ADCA5)-Pad100)") (class "Default")
      (node (ref "IC2") (pin "100") (pinfunction "PA5(ADCA5)_100") (pintype "bidirectional"))
    )
    (net (code "57") (name "unconnected-(IC2-PA6(ADCA6)-Pad1)") (class "Default")
      (node (ref "IC2") (pin "1") (pinfunction "PA6(ADCA6)_1") (pintype "bidirectional"))
    )
    (net (code "58") (name "unconnected-(IC2-PA7{slash}(ADCA7{slash}AC0-OUT)-Pad2)") (class "Default")
      (node (ref "IC2") (pin "2") (pinfunction "PA7/(ADCA7/AC0-OUT)_2") (pintype "bidirectional"))
    )
    (net (code "59") (name "unconnected-(IC2-PB0(ADCB0{slash}AREFB)-Pad5)") (class "Default")
      (node (ref "IC2") (pin "5") (pinfunction "PB0(ADCB0/AREFB)_5") (pintype "bidirectional"))
    )
    (net (code "60") (name "unconnected-(IC2-PB1(ADCB1)-Pad6)") (class "Default")
      (node (ref "IC2") (pin "6") (pinfunction "PB1(ADCB1)_6") (pintype "bidirectional"))
    )
    (net (code "61") (name "unconnected-(IC2-PB2(ADCB2{slash}DAC0)-Pad7)") (class "Default")
      (node (ref "IC2") (pin "7") (pinfunction "PB2(ADCB2/DAC0)_7") (pintype "bidirectional"))
    )
    (net (code "62") (name "unconnected-(IC2-PB3(ADCB3{slash}DAC1)-Pad8)") (class "Default")
      (node (ref "IC2") (pin "8") (pinfunction "PB3(ADCB3/DAC1)_8") (pintype "bidirectional"))
    )
    (net (code "63") (name "unconnected-(IC2-PB4(ADCB4{slash}TMS)-Pad9)") (class "Default")
      (node (ref "IC2") (pin "9") (pinfunction "PB4(ADCB4/TMS)_9") (pintype "bidirectional"))
    )
    (net (code "64") (name "unconnected-(IC2-PB5(ADCB5{slash}TDI)-Pad10)") (class "Default")
      (node (ref "IC2") (pin "10") (pinfunction "PB5(ADCB5/TDI)_10") (pintype "bidirectional"))
    )
    (net (code "65") (name "unconnected-(IC2-PB6(ADCB6{slash}TCK)-Pad11)") (class "Default")
      (node (ref "IC2") (pin "11") (pinfunction "PB6(ADCB6/TCK)_11") (pintype "bidirectional"))
    )
    (net (code "66") (name "unconnected-(IC2-PB7(ADCB7{slash}AC0-OUT{slash}TDO)-Pad12)") (class "Default")
      (node (ref "IC2") (pin "12") (pinfunction "PB7(ADCB7/AC0-OUT/TDO)_12") (pintype "bidirectional"))
    )
    (net (code "67") (name "unconnected-(IC2-PC0(OC0A{slash}SDA)-Pad15)") (class "Default")
      (node (ref "IC2") (pin "15") (pinfunction "PC0(OC0A/SDA)_15") (pintype "bidirectional"))
    )
    (net (code "68") (name "unconnected-(IC2-PC1(OC0B{slash}XCK0{slash}SCL)-Pad16)") (class "Default")
      (node (ref "IC2") (pin "16") (pinfunction "PC1(OC0B/XCK0/SCL)_16") (pintype "bidirectional"))
    )
    (net (code "69") (name "unconnected-(IC2-PC4(OC1A{slash}~{SS})-Pad19)") (class "Default")
      (node (ref "IC2") (pin "19") (pinfunction "PC4(OC1A/~{SS})_19") (pintype "bidirectional"))
    )
    (net (code "70") (name "unconnected-(IC2-PC5(OC1B{slash}MOSI{slash}XCK1)-Pad20)") (class "Default")
      (node (ref "IC2") (pin "20") (pinfunction "PC5(OC1B/MOSI/XCK1)_20") (pintype "bidirectional"))
    )
    (net (code "71") (name "unconnected-(IC2-PC6(MISO{slash}RXD1)-Pad21)") (class "Default")
      (node (ref "IC2") (pin "21") (pinfunction "PC6(MISO/RXD1)_21") (pintype "bidirectional"))
    )
    (net (code "72") (name "unconnected-(IC2-PC7(SCK{slash}TXD1{slash}CLKO{slash}EVO)-Pad22)") (class "Default")
      (node (ref "IC2") (pin "22") (pinfunction "PC7(SCK/TXD1/CLKO/EVO)_22") (pintype "bidirectional"))
    )
    (net (code "73") (name "unconnected-(IC2-PD1(OC0B{slash}XCK0{slash}SCL)-Pad26)") (class "Default")
      (node (ref "IC2") (pin "26") (pinfunction "PD1(OC0B/XCK0/SCL)_26") (pintype "bidirectional"))
    )
    (net (code "74") (name "unconnected-(IC2-PD2(OC0C{slash}RXD0)-Pad27)") (class "Default")
      (node (ref "IC2") (pin "27") (pinfunction "PD2(OC0C/RXD0)_27") (pintype "bidirectional"))
    )
    (net (code "75") (name "unconnected-(IC2-PD4(OC1A{slash}~{SS})-Pad29)") (class "Default")
      (node (ref "IC2") (pin "29") (pinfunction "PD4(OC1A/~{SS})_29") (pintype "bidirectional"))
    )
    (net (code "76") (name "unconnected-(IC2-PD5(OC1B{slash}XCK1{slash}MOSI)-Pad30)") (class "Default")
      (node (ref "IC2") (pin "30") (pinfunction "PD5(OC1B/XCK1/MOSI)_30") (pintype "bidirectional"))
    )
    (net (code "77") (name "unconnected-(IC2-PD6(RXD1{slash}MISO)-Pad31)") (class "Default")
      (node (ref "IC2") (pin "31") (pinfunction "PD6(RXD1/MISO)_31") (pintype "bidirectional"))
    )
    (net (code "78") (name "unconnected-(IC2-PD7(TXD1{slash}SCK{slash}CLKO{slash}EVO)-Pad32)") (class "Default")
      (node (ref "IC2") (pin "32") (pinfunction "PD7(TXD1/SCK/CLKO/EVO)_32") (pintype "bidirectional"))
    )
    (net (code "79") (name "unconnected-(IC2-PE0(OC0A{slash}SDA)-Pad35)") (class "Default")
      (node (ref "IC2") (pin "35") (pinfunction "PE0(OC0A/SDA)_35") (pintype "bidirectional"))
    )
    (net (code "80") (name "unconnected-(IC2-PE1(OC0B{slash}XCK0{slash}SCL)-Pad36)") (class "Default")
      (node (ref "IC2") (pin "36") (pinfunction "PE1(OC0B/XCK0/SCL)_36") (pintype "bidirectional"))
    )
    (net (code "81") (name "unconnected-(IC2-PE2(OC0C{slash}RXD0)-Pad37)") (class "Default")
      (node (ref "IC2") (pin "37") (pinfunction "PE2(OC0C/RXD0)_37") (pintype "bidirectional"))
    )
    (net (code "82") (name "unconnected-(IC2-PE3(OC0D{slash}TXD0)-Pad38)") (class "Default")
      (node (ref "IC2") (pin "38") (pinfunction "PE3(OC0D/TXD0)_38") (pintype "bidirectional"))
    )
    (net (code "83") (name "unconnected-(IC2-PE4(OC1A{slash}~{SS})-Pad39)") (class "Default")
      (node (ref "IC2") (pin "39") (pinfunction "PE4(OC1A/~{SS})_39") (pintype "bidirectional"))
    )
    (net (code "84") (name "unconnected-(IC2-PE5(OC1B{slash}XCK1{slash}MOSI)-Pad40)") (class "Default")
      (node (ref "IC2") (pin "40") (pinfunction "PE5(OC1B/XCK1/MOSI)_40") (pintype "bidirectional"))
    )
    (net (code "85") (name "unconnected-(IC2-PE6(RSC1{slash}MISO{slash}TOSC2)-Pad41)") (class "Default")
      (node (ref "IC2") (pin "41") (pinfunction "PE6(RSC1/MISO/TOSC2)_41") (pintype "bidirectional"))
    )
    (net (code "86") (name "unconnected-(IC2-PE7(TSD1{slash}SCK{slash}CLKO{slash}EVO{slash}TOSC1)-Pad42)") (class "Default")
      (node (ref "IC2") (pin "42") (pinfunction "PE7(TSD1/SCK/CLKO/EVO/TOSC1)_42") (pintype "bidirectional"))
    )
    (net (code "87") (name "unconnected-(IC2-PF2(OC0C{slash}RXD0)-Pad47)") (class "Default")
      (node (ref "IC2") (pin "47") (pinfunction "PF2(OC0C/RXD0)_47") (pintype "bidirectional"))
    )
    (net (code "88") (name "unconnected-(IC2-PF3(OC0D{slash}TXD0)-Pad48)") (class "Default")
      (node (ref "IC2") (pin "48") (pinfunction "PF3(OC0D/TXD0)_48") (pintype "bidirectional"))
    )
    (net (code "89") (name "unconnected-(IC2-PF4(OC1A{slash}~{SS})-Pad49)") (class "Default")
      (node (ref "IC2") (pin "49") (pinfunction "PF4(OC1A/~{SS})_49") (pintype "bidirectional"))
    )
    (net (code "90") (name "unconnected-(IC2-PF5(OC1B{slash}XCK1{slash}MOSI)-Pad50)") (class "Default")
      (node (ref "IC2") (pin "50") (pinfunction "PF5(OC1B/XCK1/MOSI)_50") (pintype "bidirectional"))
    )
    (net (code "91") (name "unconnected-(IC2-PH0(~{WE})-Pad55)") (class "Default")
      (node (ref "IC2") (pin "55") (pinfunction "PH0(~{WE})_55") (pintype "bidirectional"))
    )
    (net (code "92") (name "unconnected-(IC2-PH2(~{RAS}{slash}ALE1)-Pad57)") (class "Default")
      (node (ref "IC2") (pin "57") (pinfunction "PH2(~{RAS}/ALE1)_57") (pintype "bidirectional"))
    )
    (net (code "93") (name "unconnected-(IC2-PH3(~{DOM}{slash}ALE2)-Pad58)") (class "Default")
      (node (ref "IC2") (pin "58") (pinfunction "PH3(~{DOM}/ALE2)_58") (pintype "bidirectional"))
    )
    (net (code "94") (name "unconnected-(IC2-PH4(BA0{slash}~{CS0}{slash}A16)-Pad59)") (class "Default")
      (node (ref "IC2") (pin "59") (pinfunction "PH4(BA0/~{CS0}/A16)_59") (pintype "bidirectional"))
    )
    (net (code "95") (name "unconnected-(IC2-PH5(BA1{slash}~{CS1}{slash}A17)-Pad60)") (class "Default")
      (node (ref "IC2") (pin "60") (pinfunction "PH5(BA1/~{CS1}/A17)_60") (pintype "bidirectional"))
    )
    (net (code "96") (name "unconnected-(IC2-PH6(CKE{slash}~{CS2}{slash}A18)-Pad61)") (class "Default")
      (node (ref "IC2") (pin "61") (pinfunction "PH6(CKE/~{CS2}/A18)_61") (pintype "bidirectional"))
    )
    (net (code "97") (name "unconnected-(IC2-PJ0(D0{slash}A0{slash}A8)-Pad65)") (class "Default")
      (node (ref "IC2") (pin "65") (pinfunction "PJ0(D0/A0/A8)_65") (pintype "bidirectional"))
    )
    (net (code "98") (name "unconnected-(IC2-PJ1(D1{slash}A1{slash}A9)-Pad66)") (class "Default")
      (node (ref "IC2") (pin "66") (pinfunction "PJ1(D1/A1/A9)_66") (pintype "bidirectional"))
    )
    (net (code "99") (name "unconnected-(IC2-PJ2(D2{slash}A2{slash}A10)-Pad67)") (class "Default")
      (node (ref "IC2") (pin "67") (pinfunction "PJ2(D2/A2/A10)_67") (pintype "bidirectional"))
    )
    (net (code "100") (name "unconnected-(IC2-PJ4(A8{slash}D4{slash}A4{slash}A12)-Pad69)") (class "Default")
      (node (ref "IC2") (pin "69") (pinfunction "PJ4(A8/D4/A4/A12)_69") (pintype "bidirectional"))
    )
    (net (code "101") (name "unconnected-(IC2-PJ5(A9{slash}D5{slash}A5{slash}A13)-Pad70)") (class "Default")
      (node (ref "IC2") (pin "70") (pinfunction "PJ5(A9/D5/A5/A13)_70") (pintype "bidirectional"))
    )
    (net (code "102") (name "unconnected-(IC2-PJ6(A10{slash}D6{slash}A6{slash}A14)-Pad71)") (class "Default")
      (node (ref "IC2") (pin "71") (pinfunction "PJ6(A10/D6/A6/A14)_71") (pintype "bidirectional"))
    )
    (net (code "103") (name "unconnected-(IC2-PJ7(A11{slash}D7{slash}A7{slash}A15)-Pad72)") (class "Default")
      (node (ref "IC2") (pin "72") (pinfunction "PJ7(A11/D7/A7/A15)_72") (pintype "bidirectional"))
    )
    (net (code "104") (name "unconnected-(IC2-PK3(A3{slash}A11{slash}A19)-Pad78)") (class "Default")
      (node (ref "IC2") (pin "78") (pinfunction "PK3(A3/A11/A19)_78") (pintype "bidirectional"))
    )
    (net (code "105") (name "unconnected-(IC2-PK4(A4{slash}A12{slash}A20)-Pad79)") (class "Default")
      (node (ref "IC2") (pin "79") (pinfunction "PK4(A4/A12/A20)_79") (pintype "bidirectional"))
    )
    (net (code "106") (name "unconnected-(IC2-PK5(A5{slash}A13{slash}A22)-Pad80)") (class "Default")
      (node (ref "IC2") (pin "80") (pinfunction "PK5(A5/A13/A22)_80") (pintype "bidirectional"))
    )
    (net (code "107") (name "unconnected-(IC2-PK6(A6{slash}A14{slash}A22)-Pad81)") (class "Default")
      (node (ref "IC2") (pin "81") (pinfunction "PK6(A6/A14/A22)_81") (pintype "bidirectional"))
    )
    (net (code "108") (name "unconnected-(IC2-PK7(A7{slash}A15{slash}A23)-Pad82)") (class "Default")
      (node (ref "IC2") (pin "82") (pinfunction "PK7(A7/A15/A23)_82") (pintype "bidirectional"))
    )
    (net (code "109") (name "unconnected-(IC2-PQ0(TOSC1)-Pad85)") (class "Default")
      (node (ref "IC2") (pin "85") (pinfunction "PQ0(TOSC1)_85") (pintype "bidirectional"))
    )
    (net (code "110") (name "unconnected-(IC2-PQ1(TOSC2)-Pad86)") (class "Default")
      (node (ref "IC2") (pin "86") (pinfunction "PQ1(TOSC2)_86") (pintype "bidirectional"))
    )
    (net (code "111") (name "unconnected-(IC2-PQ2-Pad87)") (class "Default")
      (node (ref "IC2") (pin "87") (pinfunction "PQ2_87") (pintype "bidirectional"))
    )
    (net (code "112") (name "unconnected-(IC2-PQ3-Pad88)") (class "Default")
      (node (ref "IC2") (pin "88") (pinfunction "PQ3_88") (pintype "bidirectional"))
    )
    (net (code "113") (name "unconnected-(MIRROR_IDX-Pad4)") (class "Default")
      (node (ref "MIRROR_IDX") (pin "4") (pinfunction "4_4") (pintype "passive"))
    )
    (net (code "114") (name "unconnected-(PDI_ATMEL-NC-Pad3)") (class "Default")
      (node (ref "PDI_ATMEL") (pin "3") (pinfunction "NC_3") (pintype "passive"))
    )
    (net (code "115") (name "unconnected-(PDI_ATMEL-NC.-Pad4)") (class "Default")
      (node (ref "PDI_ATMEL") (pin "4") (pinfunction "NC._4") (pintype "passive"))
    )
  )
)
